# STLINKV2-1.net
KiCad netlist of a schematic drawn in Altium Designer
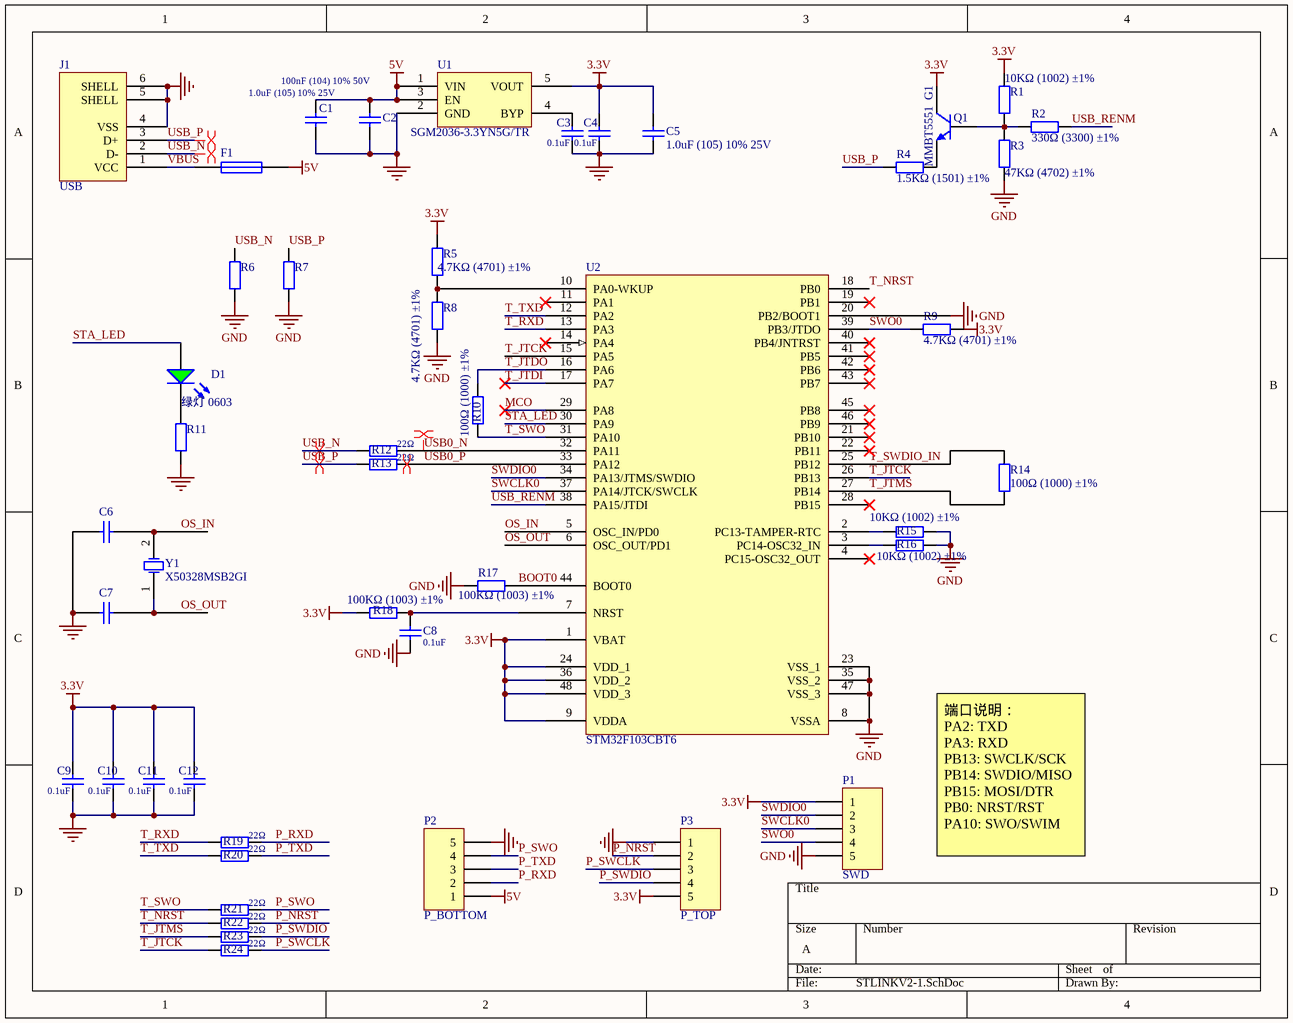
[diagram p0: STLINKV2-1.SchDoc]

(export (version "E")
  (design (tool "Eeschema 10.0.6"))
  (components
    (comp (ref "C1")
      (value "1.0uF (105) 10% 25V")
      (footprint "0402_C")
      (description "贴片电容")
      (libsource (lib "Miscellaneous Devices LC") (part "0402 1.0uF (105) 10% 25V"))
    )
    (comp (ref "C2")
      (value "100nF (104) 10% 50V")
      (footprint "0603_C")
      (description "贴片电容")
      (libsource (lib "Miscellaneous Devices LC") (part "0603 100nF (104) 10% 50V"))
    )
    (comp (ref "C3")
      (value "100nF (104) 10% 16V")
      (footprint "0402_C")
      (description "贴片电容")
      (fields (field (name "VAL") "0.1uF"))
      (libsource (lib "Miscellaneous Devices LC") (part "0402 100nF (104) 10% 16V"))
    )
    (comp (ref "C4")
      (value "100nF (104) 10% 16V")
      (footprint "0402_C")
      (description "贴片电容")
      (fields (field (name "VAL") "0.1uF"))
      (libsource (lib "Miscellaneous Devices LC") (part "0402 100nF (104) 10% 16V"))
    )
    (comp (ref "C5")
      (value "1.0uF (105) 10% 25V")
      (footprint "0402_C")
      (description "贴片电容")
      (libsource (lib "Miscellaneous Devices LC") (part "0402 1.0uF (105) 10% 25V"))
    )
    (comp (ref "C6")
      (value "20pF (200) 5% 50V")
      (footprint "0402_C")
      (description "贴片电容")
      (libsource (lib "Miscellaneous Devices LC") (part "0402 20pF (200) 5% 50V"))
    )
    (comp (ref "C7")
      (value "20pF (200) 5% 50V")
      (footprint "0402_C")
      (description "贴片电容")
      (libsource (lib "Miscellaneous Devices LC") (part "0402 20pF (200) 5% 50V"))
    )
    (comp (ref "C8")
      (value "100nF (104) 10% 16V")
      (footprint "0402_C")
      (description "贴片电容")
      (fields (field (name "VAL") "0.1uF"))
      (libsource (lib "Miscellaneous Devices LC") (part "0402 100nF (104) 10% 16V"))
    )
    (comp (ref "C9")
      (value "100nF (104) 10% 16V")
      (footprint "0402_C")
      (description "贴片电容")
      (fields (field (name "VAL") "0.1uF"))
      (libsource (lib "Miscellaneous Devices LC") (part "0402 100nF (104) 10% 16V"))
    )
    (comp (ref "C10")
      (value "100nF (104) 10% 16V")
      (footprint "0402_C")
      (description "贴片电容")
      (fields (field (name "VAL") "0.1uF"))
      (libsource (lib "Miscellaneous Devices LC") (part "0402 100nF (104) 10% 16V"))
    )
    (comp (ref "C11")
      (value "100nF (104) 10% 16V")
      (footprint "0402_C")
      (description "贴片电容")
      (fields (field (name "VAL") "0.1uF"))
      (libsource (lib "Miscellaneous Devices LC") (part "0402 100nF (104) 10% 16V"))
    )
    (comp (ref "C12")
      (value "100nF (104) 10% 16V")
      (footprint "0402_C")
      (description "贴片电容")
      (fields (field (name "VAL") "0.1uF"))
      (libsource (lib "Miscellaneous Devices LC") (part "0402 100nF (104) 10% 16V"))
    )
    (comp (ref "D1")
      (value "绿灯 0603")
      (footprint "0603_LED_S1")
      (description "发光二极管")
      (libsource (lib "Miscellaneous Devices LC") (part "0603 绿灯"))
    )
    (comp (ref "F1")
      (value "Fuse1")
      (footprint "0805-1")
      (description "保险丝")
      (libsource (lib "Fszhang") (part "Fuse1"))
    )
    (comp (ref "J1")
      (value "USB")
      (footprint "USB-B")
      (description "USB接口")
      (libsource (lib "HDR_Fszhang") (part "USB"))
    )
    (comp (ref "P1")
      (value "SWD")
      (footprint "SIP5-1.27")
      (description "Header, 5-Pin")
      (libsource (lib "Miscellaneous Connectors") (part "Header 5"))
    )
    (comp (ref "P2")
      (value "P_BOTTOM")
      (footprint "HEADER 5")
      (description "Header, 5-Pin")
      (libsource (lib "") (part "Header 5_1"))
    )
    (comp (ref "P3")
      (value "P_TOP")
      (footprint "HEADER 5")
      (description "Header, 5-Pin")
      (libsource (lib "Miscellaneous Connectors") (part "Header 5"))
    )
    (comp (ref "Q1")
      (value "MMBT5551  G1")
      (footprint "SOT-23(SOT-23-3)")
      (description "三极管")
      (libsource (lib "Miscellaneous Devices LC") (part "SOT-23 MMBT5551  G1"))
    )
    (comp (ref "R1")
      (value "10KΩ (1002) ±1%")
      (footprint "0402_R")
      (description "贴片电阻")
      (libsource (lib "") (part "0402 10KΩ (1002) 1%_1"))
    )
    (comp (ref "R2")
      (value "330Ω (3300) ±1%")
      (footprint "0402_R")
      (description "贴片电阻")
      (libsource (lib "Miscellaneous Devices LC") (part "0402 330Ω (3300) 1%"))
    )
    (comp (ref "R3")
      (value "47KΩ (4702) ±1%")
      (footprint "0402_R")
      (description "贴片电阻")
      (libsource (lib "Miscellaneous Devices LC") (part "0402 47KΩ (4702) 1%"))
    )
    (comp (ref "R4")
      (value "1.5KΩ (1501) ±1%")
      (footprint "0402_R")
      (description "贴片电阻")
      (libsource (lib "Miscellaneous Devices LC") (part "0402 1.5KΩ (1501) 1%"))
    )
    (comp (ref "R5")
      (value "4.7KΩ (4701) ±1%")
      (footprint "0402_R")
      (description "贴片电阻")
      (libsource (lib "Miscellaneous Devices LC") (part "0402 4.7KΩ (4701) 1%"))
    )
    (comp (ref "R6")
      (value "1MΩ (1004) ±1%")
      (footprint "0402_R")
      (description "TVS")
      (libsource (lib "Miscellaneous Devices LC") (part "0402 1MΩ (1004) 1%"))
    )
    (comp (ref "R7")
      (value "1MΩ (1004) ±1%")
      (footprint "0402_R")
      (description "TVS")
      (libsource (lib "Miscellaneous Devices LC") (part "0402 1MΩ (1004) 1%"))
    )
    (comp (ref "R8")
      (value "4.7KΩ (4701) ±1%")
      (footprint "0402_R")
      (description "贴片电阻")
      (libsource (lib "Miscellaneous Devices LC") (part "0402 4.7KΩ (4701) 1%"))
    )
    (comp (ref "R9")
      (value "4.7KΩ (4701) ±1%")
      (footprint "0402_R")
      (description "贴片电阻")
      (libsource (lib "") (part "0402 4.7KΩ (4701) 1%_1"))
    )
    (comp (ref "R10")
      (value "100Ω (1000) ±1%")
      (footprint "0402_R")
      (description "贴片电阻")
      (libsource (lib "") (part "0402 100Ω (1000) 1%_1"))
    )
    (comp (ref "R11")
      (value "2.2KΩ (2201) ±1%")
      (footprint "0402_R")
      (description "贴片电阻")
      (libsource (lib "Miscellaneous Devices LC") (part "0402 2.2KΩ (2201) 1%"))
    )
    (comp (ref "R12")
      (value "22Ω (22R0) ±1%")
      (footprint "0402_R")
      (description "贴片电阻")
      (fields (field (name "VAL") "22Ω"))
      (libsource (lib "Miscellaneous Devices LC") (part "0402 22Ω (22R0) 1%"))
    )
    (comp (ref "R13")
      (value "22Ω (22R0) ±1%")
      (footprint "0402_R")
      (description "贴片电阻")
      (fields (field (name "VAL") "22Ω"))
      (libsource (lib "Miscellaneous Devices LC") (part "0402 22Ω (22R0) 1%"))
    )
    (comp (ref "R14")
      (value "100Ω (1000) ±1%")
      (footprint "0402_R")
      (description "贴片电阻")
      (libsource (lib "Miscellaneous Devices LC") (part "0402 100Ω (1000) 1%"))
    )
    (comp (ref "R15")
      (value "10KΩ (1002) ±1%")
      (footprint "0402_R")
      (description "贴片电阻")
      (libsource (lib "Miscellaneous Devices LC") (part "0402 10KΩ (1002) 1%"))
    )
    (comp (ref "R16")
      (value "10KΩ (1002) ±1%")
      (footprint "0402_R")
      (description "贴片电阻")
      (libsource (lib "Miscellaneous Devices LC") (part "0402 10KΩ (1002) 1%"))
    )
    (comp (ref "R17")
      (value "100KΩ (1003) ±1%")
      (footprint "0402_R")
      (description "贴片电阻")
      (libsource (lib "Miscellaneous Devices LC") (part "0402 100KΩ (1003) 1%"))
    )
    (comp (ref "R18")
      (value "100KΩ (1003) ±1%")
      (footprint "0402_R")
      (description "贴片电阻")
      (libsource (lib "Miscellaneous Devices LC") (part "0402 100KΩ (1003) 1%"))
    )
    (comp (ref "R19")
      (value "22Ω (22R0) ±1%")
      (footprint "0402_R")
      (description "贴片电阻")
      (fields (field (name "VAL") "22Ω"))
      (libsource (lib "Miscellaneous Devices LC") (part "0402 22Ω (22R0) 1%"))
    )
    (comp (ref "R20")
      (value "22Ω (22R0) ±1%")
      (footprint "0402_R")
      (description "贴片电阻")
      (fields (field (name "VAL") "22Ω"))
      (libsource (lib "Miscellaneous Devices LC") (part "0402 22Ω (22R0) 1%"))
    )
    (comp (ref "R21")
      (value "22Ω (22R0) ±1%")
      (footprint "0402_R")
      (description "贴片电阻")
      (fields (field (name "VAL") "22Ω"))
      (libsource (lib "Miscellaneous Devices LC") (part "0402 22Ω (22R0) 1%"))
    )
    (comp (ref "R22")
      (value "22Ω (22R0) ±1%")
      (footprint "0402_R")
      (description "贴片电阻")
      (fields (field (name "VAL") "22Ω"))
      (libsource (lib "Miscellaneous Devices LC") (part "0402 22Ω (22R0) 1%"))
    )
    (comp (ref "R23")
      (value "22Ω (22R0) ±1%")
      (footprint "0402_R")
      (description "贴片电阻")
      (fields (field (name "VAL") "22Ω"))
      (libsource (lib "Miscellaneous Devices LC") (part "0402 22Ω (22R0) 1%"))
    )
    (comp (ref "R24")
      (value "22Ω (22R0) ±1%")
      (footprint "0402_R")
      (description "贴片电阻")
      (fields (field (name "VAL") "22Ω"))
      (libsource (lib "Miscellaneous Devices LC") (part "0402 22Ω (22R0) 1%"))
    )
    (comp (ref "U1")
      (value "SGM2036-3.3YN5G/TR")
      (footprint "SOT23-5")
      (description "低压差线性稳压(LDO)")
      (libsource (lib "Schlib1") (part "SPX3819"))
    )
    (comp (ref "U2")
      (value "STM32F103CBT6")
      (footprint "LQFP-48_7x7x05P")
      (description "STM32 ARM-based 32-bit MCU with 64 Kbytes Flash, 48-pin LQFP, Industrial Temperature")
      (libsource (lib "ST Microcontroller 32-Bit STM32") (part "STM32F103C8T6"))
    )
    (comp (ref "Y1")
      (value "X50328MSB2GI")
      (footprint "SMD-5032_2P")
      (description "贴片无源晶振8MHz ±20ppm 20pF")
      (libsource (lib "Miscellaneous Devices LC") (part "SMD-5032_2P 8MHz 20ppm 20pF"))
    )
  )
  (nets
    (net (code "1") (name "/BOOT0") (class "Default")
      (node (ref "R17") (pin "2") (pinfunction "2_2") (pintype "passive"))
      (node (ref "U2") (pin "44") (pinfunction "BOOT0_44") (pintype "passive"))
    )
    (net (code "2") (name "/MCO") (class "Default")
      (node (ref "U2") (pin "29") (pinfunction "PA8_29") (pintype "passive+no_connect"))
    )
    (net (code "3") (name "/OS_IN") (class "Default")
      (node (ref "C6") (pin "2") (pinfunction "2_2") (pintype "passive"))
      (node (ref "U2") (pin "5") (pinfunction "OSC_IN/PD0_5") (pintype "passive"))
      (node (ref "Y1") (pin "2") (pinfunction "OSC2_2") (pintype "passive"))
    )
    (net (code "4") (name "/OS_OUT") (class "Default")
      (node (ref "C7") (pin "2") (pinfunction "2_2") (pintype "passive"))
      (node (ref "U2") (pin "6") (pinfunction "OSC_OUT/PD1_6") (pintype "passive"))
      (node (ref "Y1") (pin "1") (pinfunction "OSC1_1") (pintype "passive"))
    )
    (net (code "5") (name "/P_NRST") (class "Default")
      (node (ref "P3") (pin "2") (pinfunction "2_2") (pintype "passive"))
      (node (ref "R22") (pin "2") (pinfunction "2_2") (pintype "passive"))
    )
    (net (code "6") (name "/P_RXD") (class "Default")
      (node (ref "P2") (pin "2") (pinfunction "2_2") (pintype "passive"))
      (node (ref "R19") (pin "2") (pinfunction "2_2") (pintype "passive"))
    )
    (net (code "7") (name "/P_SWCLK") (class "Default")
      (node (ref "P3") (pin "3") (pinfunction "3_3") (pintype "passive"))
      (node (ref "R24") (pin "2") (pinfunction "2_2") (pintype "passive"))
    )
    (net (code "8") (name "/P_SWDIO") (class "Default")
      (node (ref "P3") (pin "4") (pinfunction "4_4") (pintype "passive"))
      (node (ref "R23") (pin "2") (pinfunction "2_2") (pintype "passive"))
    )
    (net (code "9") (name "/P_SWO") (class "Default")
      (node (ref "P2") (pin "4") (pinfunction "4_4") (pintype "passive"))
      (node (ref "R21") (pin "2") (pinfunction "2_2") (pintype "passive"))
    )
    (net (code "10") (name "/P_TXD") (class "Default")
      (node (ref "P2") (pin "3") (pinfunction "3_3") (pintype "passive"))
      (node (ref "R20") (pin "2") (pinfunction "2_2") (pintype "passive"))
    )
    (net (code "11") (name "/STA_LED") (class "Default")
      (node (ref "D1") (pin "A") (pinfunction "A_A") (pintype "passive"))
      (node (ref "U2") (pin "30") (pinfunction "PA9_30") (pintype "passive"))
    )
    (net (code "12") (name "/SWCLK0") (class "Default")
      (node (ref "P1") (pin "3") (pinfunction "3_3") (pintype "passive"))
      (node (ref "U2") (pin "37") (pinfunction "PA14/JTCK/SWCLK_37") (pintype "passive"))
    )
    (net (code "13") (name "/SWDIO0") (class "Default")
      (node (ref "P1") (pin "2") (pinfunction "2_2") (pintype "passive"))
      (node (ref "U2") (pin "34") (pinfunction "PA13/JTMS/SWDIO_34") (pintype "passive"))
    )
    (net (code "14") (name "/SWO0") (class "Default")
      (node (ref "P1") (pin "4") (pinfunction "4_4") (pintype "passive"))
      (node (ref "R9") (pin "1") (pinfunction "1_1") (pintype "passive"))
      (node (ref "U2") (pin "39") (pinfunction "PB3/JTDO_39") (pintype "passive"))
    )
    (net (code "15") (name "/T_JTCK") (class "Default")
      (node (ref "R24") (pin "1") (pinfunction "1_1") (pintype "passive"))
      (node (ref "U2") (pin "15") (pinfunction "PA5_15") (pintype "passive"))
      (node (ref "U2") (pin "26") (pinfunction "PB13_26") (pintype "passive"))
    )
    (net (code "16") (name "/T_JTDI") (class "Default")
      (node (ref "U2") (pin "17") (pinfunction "PA7_17") (pintype "passive+no_connect"))
    )
    (net (code "17") (name "/T_JTDO") (class "Default")
      (node (ref "R10") (pin "1") (pinfunction "1_1") (pintype "passive"))
      (node (ref "U2") (pin "16") (pinfunction "PA6_16") (pintype "passive"))
    )
    (net (code "18") (name "/T_JTMS") (class "Default")
      (node (ref "R14") (pin "1") (pinfunction "1_1") (pintype "passive"))
      (node (ref "R23") (pin "1") (pinfunction "1_1") (pintype "passive"))
      (node (ref "U2") (pin "27") (pinfunction "PB14_27") (pintype "passive"))
    )
    (net (code "19") (name "/T_NRST") (class "Default")
      (node (ref "R22") (pin "1") (pinfunction "1_1") (pintype "passive"))
      (node (ref "U2") (pin "18") (pinfunction "PB0_18") (pintype "passive"))
    )
    (net (code "20") (name "/T_RXD") (class "Default")
      (node (ref "R19") (pin "1") (pinfunction "1_1") (pintype "passive"))
      (node (ref "U2") (pin "13") (pinfunction "PA3_13") (pintype "passive"))
    )
    (net (code "21") (name "/T_SWDIO_IN") (class "Default")
      (node (ref "R14") (pin "2") (pinfunction "2_2") (pintype "passive"))
      (node (ref "U2") (pin "25") (pinfunction "PB12_25") (pintype "passive"))
    )
    (net (code "22") (name "/T_SWO") (class "Default")
      (node (ref "R10") (pin "2") (pinfunction "2_2") (pintype "passive"))
      (node (ref "R21") (pin "1") (pinfunction "1_1") (pintype "passive"))
      (node (ref "U2") (pin "31") (pinfunction "PA10_31") (pintype "passive"))
    )
    (net (code "23") (name "/T_TXD") (class "Default")
      (node (ref "R20") (pin "1") (pinfunction "1_1") (pintype "passive"))
      (node (ref "U2") (pin "12") (pinfunction "PA2_12") (pintype "passive"))
    )
    (net (code "24") (name "/USB0_N") (class "Default")
      (node (ref "R12") (pin "2") (pinfunction "2_2") (pintype "passive"))
      (node (ref "U2") (pin "32") (pinfunction "PA11_32") (pintype "passive"))
    )
    (net (code "25") (name "/USB0_P") (class "Default")
      (node (ref "R13") (pin "2") (pinfunction "2_2") (pintype "passive"))
      (node (ref "U2") (pin "33") (pinfunction "PA12_33") (pintype "passive"))
    )
    (net (code "26") (name "/USB_N") (class "Default")
      (node (ref "J1") (pin "2") (pinfunction "D-_2") (pintype "passive"))
      (node (ref "R12") (pin "1") (pinfunction "1_1") (pintype "passive"))
      (node (ref "R6") (pin "2") (pinfunction "2_2") (pintype "passive"))
    )
    (net (code "27") (name "/USB_P") (class "Default")
      (node (ref "J1") (pin "3") (pinfunction "D+_3") (pintype "passive"))
      (node (ref "R13") (pin "1") (pinfunction "1_1") (pintype "passive"))
      (node (ref "R4") (pin "1") (pinfunction "1_1") (pintype "passive"))
      (node (ref "R7") (pin "2") (pinfunction "2_2") (pintype "passive"))
    )
    (net (code "28") (name "/USB_RENM") (class "Default")
      (node (ref "R2") (pin "2") (pinfunction "2_2") (pintype "passive"))
      (node (ref "U2") (pin "38") (pinfunction "PA15/JTDI_38") (pintype "passive"))
    )
    (net (code "29") (name "/VBUS") (class "Default")
      (node (ref "F1") (pin "2") (pinfunction "2_2") (pintype "passive"))
      (node (ref "J1") (pin "1") (pinfunction "VCC_1") (pintype "passive"))
    )
    (net (code "30") (name "3.3V") (class "Default")
      (node (ref "C10") (pin "2") (pinfunction "2_2") (pintype "passive"))
      (node (ref "C11") (pin "2") (pinfunction "2_2") (pintype "passive"))
      (node (ref "C12") (pin "2") (pinfunction "2_2") (pintype "passive"))
      (node (ref "C4") (pin "2") (pinfunction "2_2") (pintype "passive"))
      (node (ref "C5") (pin "2") (pinfunction "2_2") (pintype "passive"))
      (node (ref "C9") (pin "2") (pinfunction "2_2") (pintype "passive"))
      (node (ref "P1") (pin "1") (pinfunction "1_1") (pintype "passive"))
      (node (ref "P3") (pin "5") (pinfunction "5_5") (pintype "passive"))
      (node (ref "Q1") (pin "3") (pinfunction "C_3") (pintype "passive"))
      (node (ref "R1") (pin "2") (pinfunction "2_2") (pintype "passive"))
      (node (ref "R18") (pin "1") (pinfunction "1_1") (pintype "passive"))
      (node (ref "R5") (pin "2") (pinfunction "2_2") (pintype "passive"))
      (node (ref "R9") (pin "2") (pinfunction "2_2") (pintype "passive"))
      (node (ref "U1") (pin "5") (pinfunction "VOUT_5") (pintype "passive"))
      (node (ref "U2") (pin "1") (pinfunction "VBAT_1") (pintype "passive"))
      (node (ref "U2") (pin "24") (pinfunction "VDD_1_24") (pintype "passive"))
      (node (ref "U2") (pin "36") (pinfunction "VDD_2_36") (pintype "passive"))
      (node (ref "U2") (pin "48") (pinfunction "VDD_3_48") (pintype "passive"))
      (node (ref "U2") (pin "9") (pinfunction "VDDA_9") (pintype "passive"))
    )
    (net (code "31") (name "5V") (class "Default")
      (node (ref "C1") (pin "2") (pinfunction "2_2") (pintype "passive"))
      (node (ref "C2") (pin "2") (pinfunction "2_2") (pintype "passive"))
      (node (ref "F1") (pin "1") (pinfunction "1_1") (pintype "passive"))
      (node (ref "P2") (pin "1") (pinfunction "1_1") (pintype "passive"))
      (node (ref "U1") (pin "1") (pinfunction "VIN_1") (pintype "passive"))
      (node (ref "U1") (pin "3") (pinfunction "EN_3") (pintype "passive"))
    )
    (net (code "32") (name "GND") (class "Default")
      (node (ref "C1") (pin "1") (pinfunction "1_1") (pintype "passive"))
      (node (ref "C10") (pin "1") (pinfunction "1_1") (pintype "passive"))
      (node (ref "C11") (pin "1") (pinfunction "1_1") (pintype "passive"))
      (node (ref "C12") (pin "1") (pinfunction "1_1") (pintype "passive"))
      (node (ref "C2") (pin "1") (pinfunction "1_1") (pintype "passive"))
      (node (ref "C3") (pin "1") (pinfunction "1_1") (pintype "passive"))
      (node (ref "C4") (pin "1") (pinfunction "1_1") (pintype "passive"))
      (node (ref "C5") (pin "1") (pinfunction "1_1") (pintype "passive"))
      (node (ref "C6") (pin "1") (pinfunction "1_1") (pintype "passive"))
      (node (ref "C7") (pin "1") (pinfunction "1_1") (pintype "passive"))
      (node (ref "C8") (pin "2") (pinfunction "2_2") (pintype "passive"))
      (node (ref "C9") (pin "1") (pinfunction "1_1") (pintype "passive"))
      (node (ref "J1") (pin "4") (pinfunction "VSS_4") (pintype "passive"))
      (node (ref "J1") (pin "5") (pinfunction "SHELL_5") (pintype "passive"))
      (node (ref "J1") (pin "6") (pinfunction "SHELL_6") (pintype "passive"))
      (node (ref "P1") (pin "5") (pinfunction "5_5") (pintype "passive"))
      (node (ref "P2") (pin "5") (pinfunction "5_5") (pintype "passive"))
      (node (ref "P3") (pin "1") (pinfunction "1_1") (pintype "passive"))
      (node (ref "R11") (pin "1") (pinfunction "1_1") (pintype "passive"))
      (node (ref "R15") (pin "2") (pinfunction "2_2") (pintype "passive"))
      (node (ref "R16") (pin "2") (pinfunction "2_2") (pintype "passive"))
      (node (ref "R17") (pin "1") (pinfunction "1_1") (pintype "passive"))
      (node (ref "R3") (pin "1") (pinfunction "1_1") (pintype "passive"))
      (node (ref "R6") (pin "1") (pinfunction "1_1") (pintype "passive"))
      (node (ref "R7") (pin "1") (pinfunction "1_1") (pintype "passive"))
      (node (ref "R8") (pin "1") (pinfunction "1_1") (pintype "passive"))
      (node (ref "U1") (pin "2") (pinfunction "GND_2") (pintype "passive"))
      (node (ref "U2") (pin "20") (pinfunction "PB2/BOOT1_20") (pintype "passive"))
      (node (ref "U2") (pin "23") (pinfunction "VSS_1_23") (pintype "passive"))
      (node (ref "U2") (pin "35") (pinfunction "VSS_2_35") (pintype "passive"))
      (node (ref "U2") (pin "47") (pinfunction "VSS_3_47") (pintype "passive"))
      (node (ref "U2") (pin "8") (pinfunction "VSSA_8") (pintype "passive"))
    )
    (net (code "33") (name "Net-(D1-PadK)") (class "Default")
      (node (ref "D1") (pin "K") (pinfunction "K_K") (pintype "passive"))
      (node (ref "R11") (pin "2") (pinfunction "2_2") (pintype "passive"))
    )
    (net (code "34") (name "Net-(Q1-B)") (class "Default")
      (node (ref "Q1") (pin "1") (pinfunction "B_1") (pintype "passive"))
      (node (ref "R1") (pin "1") (pinfunction "1_1") (pintype "passive"))
      (node (ref "R2") (pin "1") (pinfunction "1_1") (pintype "passive"))
      (node (ref "R3") (pin "2") (pinfunction "2_2") (pintype "passive"))
    )
    (net (code "35") (name "Net-(Q1-E)") (class "Default")
      (node (ref "Q1") (pin "2") (pinfunction "E_2") (pintype "passive"))
      (node (ref "R4") (pin "2") (pinfunction "2_2") (pintype "passive"))
    )
    (net (code "36") (name "Net-(U1-BYP)") (class "Default")
      (node (ref "C3") (pin "2") (pinfunction "2_2") (pintype "passive"))
      (node (ref "U1") (pin "4") (pinfunction "BYP_4") (pintype "passive"))
    )
    (net (code "37") (name "Net-(U2-NRST)") (class "Default")
      (node (ref "C8") (pin "1") (pinfunction "1_1") (pintype "passive"))
      (node (ref "R18") (pin "2") (pinfunction "2_2") (pintype "passive"))
      (node (ref "U2") (pin "7") (pinfunction "NRST_7") (pintype "passive"))
    )
    (net (code "38") (name "Net-(U2-PA0-WKUP)") (class "Default")
      (node (ref "R5") (pin "1") (pinfunction "1_1") (pintype "passive"))
      (node (ref "R8") (pin "2") (pinfunction "2_2") (pintype "passive"))
      (node (ref "U2") (pin "10") (pinfunction "PA0-WKUP_10") (pintype "passive"))
    )
    (net (code "39") (name "Net-(U2-PC13-TAMPER-RTC)") (class "Default")
      (node (ref "R15") (pin "1") (pinfunction "1_1") (pintype "passive"))
      (node (ref "U2") (pin "2") (pinfunction "PC13-TAMPER-RTC_2") (pintype "passive"))
    )
    (net (code "40") (name "Net-(U2-PC14-OSC32_IN)") (class "Default")
      (node (ref "R16") (pin "1") (pinfunction "1_1") (pintype "passive"))
      (node (ref "U2") (pin "3") (pinfunction "PC14-OSC32_IN_3") (pintype "passive"))
    )
    (net (code "41") (name "unconnected-(U2-PA1-Pad11)") (class "Default")
      (node (ref "U2") (pin "11") (pinfunction "PA1_11") (pintype "passive+no_connect"))
    )
    (net (code "42") (name "unconnected-(U2-PA4-Pad14)") (class "Default")
      (node (ref "U2") (pin "14") (pinfunction "PA4_14") (pintype "input+no_connect"))
    )
    (net (code "43") (name "unconnected-(U2-PB1-Pad19)") (class "Default")
      (node (ref "U2") (pin "19") (pinfunction "PB1_19") (pintype "passive+no_connect"))
    )
    (net (code "44") (name "unconnected-(U2-PB4{slash}JNTRST-Pad40)") (class "Default")
      (node (ref "U2") (pin "40") (pinfunction "PB4/JNTRST_40") (pintype "passive+no_connect"))
    )
    (net (code "45") (name "unconnected-(U2-PB5-Pad41)") (class "Default")
      (node (ref "U2") (pin "41") (pinfunction "PB5_41") (pintype "passive+no_connect"))
    )
    (net (code "46") (name "unconnected-(U2-PB6-Pad42)") (class "Default")
      (node (ref "U2") (pin "42") (pinfunction "PB6_42") (pintype "passive+no_connect"))
    )
    (net (code "47") (name "unconnected-(U2-PB7-Pad43)") (class "Default")
      (node (ref "U2") (pin "43") (pinfunction "PB7_43") (pintype "passive+no_connect"))
    )
    (net (code "48") (name "unconnected-(U2-PB8-Pad45)") (class "Default")
      (node (ref "U2") (pin "45") (pinfunction "PB8_45") (pintype "passive+no_connect"))
    )
    (net (code "49") (name "unconnected-(U2-PB9-Pad46)") (class "Default")
      (node (ref "U2") (pin "46") (pinfunction "PB9_46") (pintype "passive+no_connect"))
    )
    (net (code "50") (name "unconnected-(U2-PB10-Pad21)") (class "Default")
      (node (ref "U2") (pin "21") (pinfunction "PB10_21") (pintype "passive+no_connect"))
    )
    (net (code "51") (name "unconnected-(U2-PB11-Pad22)") (class "Default")
      (node (ref "U2") (pin "22") (pinfunction "PB11_22") (pintype "passive+no_connect"))
    )
    (net (code "52") (name "unconnected-(U2-PB15-Pad28)") (class "Default")
      (node (ref "U2") (pin "28") (pinfunction "PB15_28") (pintype "passive+no_connect"))
    )
    (net (code "53") (name "unconnected-(U2-PC15-OSC32_OUT-Pad4)") (class "Default")
      (node (ref "U2") (pin "4") (pinfunction "PC15-OSC32_OUT_4") (pintype "passive+no_connect"))
    )
  )
)
